# 4_Sonda_wzmacniacz.net
KiCad netlist of a schematic drawn in Altium Designer
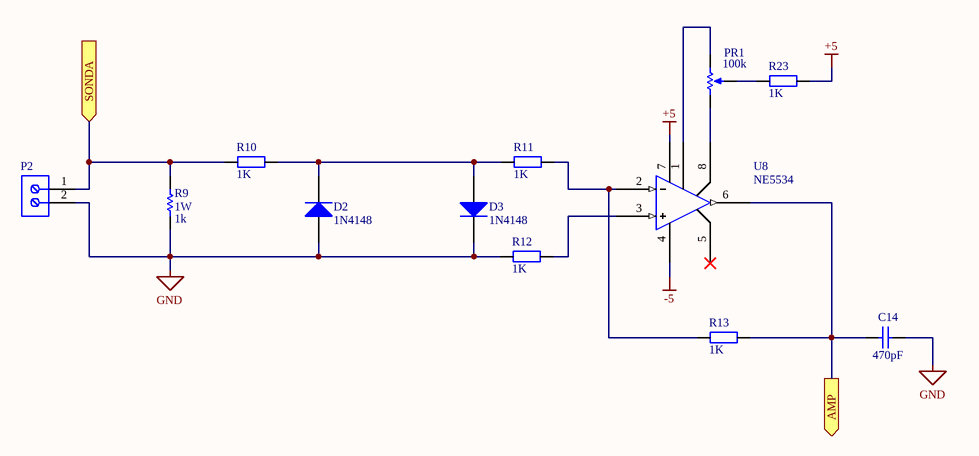
[diagram p0: 4_Sonda+wzmacniacz.SchDoc]

(export (version "E")
  (design (tool "Eeschema 10.0.6"))
  (components
    (comp (ref "C14")
      (value "CC-470@TME")
      (footprint "KEMT-C315-THT-2")
      (description "Capacitor, Ceramic, 22 pF, +/-10 %, 100 V, -55 to 125 degC, 2-Pin THD, RoHS, Bulk")
      (fields (field (name "CAPACITANCE") "470pF"))
      (libsource (lib "Altium Content Vault") (part "CAP-NP-2"))
    )
    (comp (ref "D2")
      (value "1N4148")
      (footprint "DIOD-SOD323-2-A_V")
      (libsource (lib "Altium Content Vault") (part "D-AK-2"))
    )
    (comp (ref "D3")
      (value "1N4148")
      (footprint "DIOD-SOD323-2-A_V")
      (libsource (lib "Altium Content Vault") (part "D-AK-2"))
    )
    (comp (ref "P2")
      (value "282836-2 / SONDA")
      (footprint "TECO-282836-2_V")
      (description "Female Header, Pitch 5 mm, 1 x 2 Position, Height 10 mm, Tail Length 3.5 mm, Rohs, Bulk")
      (fields (field (name "VOLTAGE") "300V") (field (name "MANUFACTURER") "TE Connectivity"))
      (libsource (lib "Altium Content Vault") (part "CN-1P-F-TB2"))
    )
    (comp (ref "PR1")
      (value "3296W-1-104LF@TME")
      (footprint "BOUR-3296W")
      (fields (field (name "RESISTANCE") "100k") (field (name "TOLERANCE") "1%"))
      (libsource (lib "Altium Content Vault") (part "RES-POT-3"))
    )
    (comp (ref "R9")
      (value "1W")
      (footprint "OMTE-RES7X2.5-2")
      (fields
        (field (name "RESISTANCE (OHMS)") "1k")
        (field (name "TOLERANCE") "±5%")
        (field (name "PARTNUMBER") "OD103JE")
        (field (name "MANUFACTURER") "Ohmite")
      )
      (libsource (lib "Altium Content Vault") (part "RES-2"))
    )
    (comp (ref "R10")
      (value "1K")
      (footprint "R1206")
      (description "Resistor")
      (libsource (lib "MT_Library") (part "Res"))
    )
    (comp (ref "R11")
      (value "1K")
      (footprint "R1206")
      (description "Resistor")
      (libsource (lib "MT_Library") (part "Res"))
    )
    (comp (ref "R12")
      (value "1K")
      (footprint "R1206")
      (description "Resistor")
      (libsource (lib "MT_Library") (part "Res"))
    )
    (comp (ref "R13")
      (value "1K")
      (footprint "R1206")
      (description "Resistor")
      (libsource (lib "MT_Library") (part "Res"))
    )
    (comp (ref "R23")
      (value "1K")
      (footprint "R1206")
      (description "Resistor")
      (libsource (lib "MT_Library") (part "Res"))
    )
    (comp (ref "U8")
      (value "NE5534")
      (footprint "NE5534 FIXED")
      (libsource (lib "MT_Library") (part "NE5534"))
    )
  )
  (nets
    (net (code "1") (name "+5") (class "Default")
      (node (ref "R23") (pin "2") (pinfunction "2_2") (pintype "passive"))
      (node (ref "U8") (pin "7") (pinfunction "VCC+_7") (pintype "power_in"))
    )
    (net (code "2") (name "-5") (class "Default")
      (node (ref "U8") (pin "4") (pinfunction "VCC-_4") (pintype "power_in"))
    )
    (net (code "3") (name "/AMP") (class "Default")
      (node (ref "C14") (pin "1") (pinfunction "1_1") (pintype "passive"))
      (node (ref "R13") (pin "2") (pinfunction "2_2") (pintype "passive"))
      (node (ref "U8") (pin "6") (pinfunction "OUT_6") (pintype "output"))
    )
    (net (code "4") (name "/SONDA") (class "Default")
      (node (ref "P2") (pin "1") (pinfunction "1_1") (pintype "passive"))
      (node (ref "R10") (pin "1") (pinfunction "1_1") (pintype "passive"))
      (node (ref "R9") (pin "2") (pinfunction "2_2") (pintype "passive"))
    )
    (net (code "5") (name "GND") (class "Default")
      (node (ref "C14") (pin "2") (pinfunction "2_2") (pintype "passive"))
      (node (ref "D2") (pin "1") (pinfunction "A_1") (pintype "passive"))
      (node (ref "D3") (pin "2") (pinfunction "K_2") (pintype "passive"))
      (node (ref "P2") (pin "2") (pinfunction "2_2") (pintype "passive"))
      (node (ref "R12") (pin "1") (pinfunction "1_1") (pintype "passive"))
      (node (ref "R9") (pin "1") (pinfunction "1_1") (pintype "passive"))
    )
    (net (code "6") (name "Net-(D2-K)") (class "Default")
      (node (ref "D2") (pin "2") (pinfunction "K_2") (pintype "passive"))
      (node (ref "D3") (pin "1") (pinfunction "A_1") (pintype "passive"))
      (node (ref "R10") (pin "2") (pinfunction "2_2") (pintype "passive"))
      (node (ref "R11") (pin "1") (pinfunction "1_1") (pintype "passive"))
    )
    (net (code "7") (name "Net-(PR1-CCW)") (class "Default")
      (node (ref "PR1") (pin "1") (pinfunction "CCW_1") (pintype "passive"))
      (node (ref "U8") (pin "8") (pinfunction "COMP/BAL_8") (pintype "passive"))
    )
    (net (code "8") (name "Net-(PR1-CW)") (class "Default")
      (node (ref "PR1") (pin "3") (pinfunction "CW_3") (pintype "passive"))
      (node (ref "U8") (pin "1") (pinfunction "BALANCE_1") (pintype "passive"))
    )
    (net (code "9") (name "Net-(PR1-S)") (class "Default")
      (node (ref "PR1") (pin "2") (pinfunction "S_2") (pintype "passive"))
      (node (ref "R23") (pin "1") (pinfunction "1_1") (pintype "passive"))
    )
    (net (code "10") (name "Net-(U8-IN+)") (class "Default")
      (node (ref "R12") (pin "2") (pinfunction "2_2") (pintype "passive"))
      (node (ref "U8") (pin "3") (pinfunction "IN+_3") (pintype "input"))
    )
    (net (code "11") (name "Net-(U8-IN-)") (class "Default")
      (node (ref "R11") (pin "2") (pinfunction "2_2") (pintype "passive"))
      (node (ref "R13") (pin "1") (pinfunction "1_1") (pintype "passive"))
      (node (ref "U8") (pin "2") (pinfunction "IN-_2") (pintype "input"))
    )
    (net (code "12") (name "unconnected-(U8-COMP-Pad5)") (class "Default")
      (node (ref "U8") (pin "5") (pinfunction "COMP_5") (pintype "passive+no_connect"))
    )
  )
)
